# icetube_main.net
KiCad netlist of a schematic drawn in EAGLE
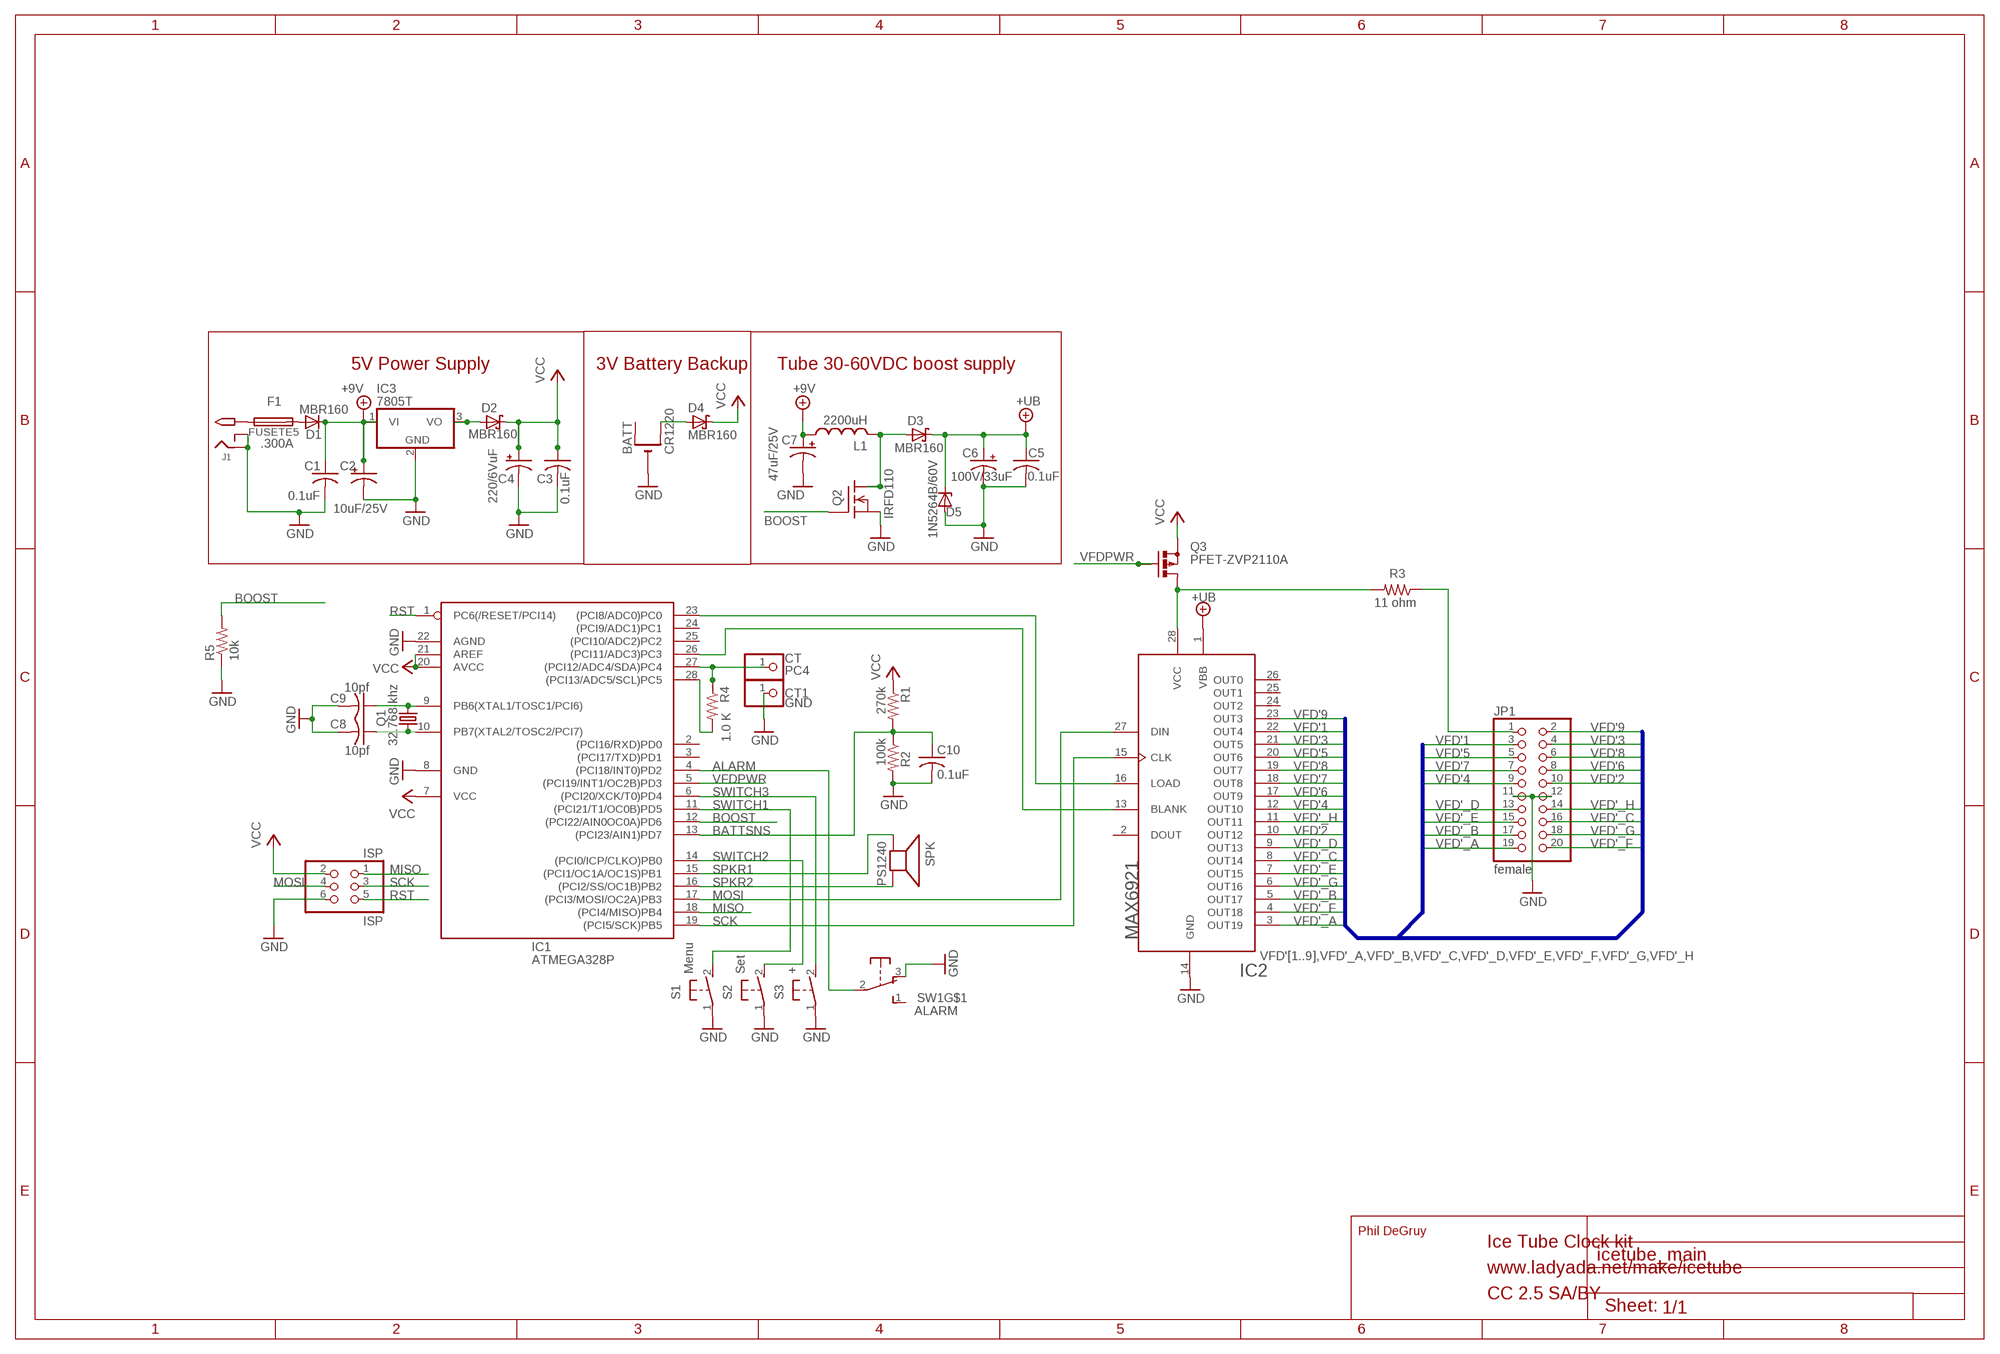
[diagram p0: schematic, sheet 1]

(export (version "E")
  (design (tool "Eeschema 10.0.6"))
  (components
    (comp (ref "BATT")
      (value "CR1220")
      (footprint "eagle-import:CR1220-THM")
      (libsource (lib "eagle-import") (part "CR1220THM"))
    )
    (comp (ref "C1")
      (value "0.1uF")
      (footprint "eagle-import:C025-025X050")
      (libsource (lib "eagle-import") (part "C-US025-025X050"))
    )
    (comp (ref "C2")
      (value "10uF/25V")
      (footprint "eagle-import:E2,5-6")
      (libsource (lib "eagle-import") (part "CPOL-USE2.5-6"))
    )
    (comp (ref "C3")
      (value "0.1uF")
      (footprint "eagle-import:C025-025X050")
      (libsource (lib "eagle-import") (part "C-US025-025X050"))
    )
    (comp (ref "C4")
      (value "220/6VuF")
      (footprint "eagle-import:E2,5-6")
      (libsource (lib "eagle-import") (part "CPOL-USE2.5-6"))
    )
    (comp (ref "C5")
      (value "0.1uF")
      (footprint "eagle-import:C025-024X044")
      (libsource (lib "eagle-import") (part "rcl-ez_C-US025-024X044"))
    )
    (comp (ref "C6")
      (value "100V/33uF")
      (footprint "eagle-import:E3,5-8")
      (libsource (lib "eagle-import") (part "rcl-ez_CPOL-USE3.5-8"))
    )
    (comp (ref "C7")
      (value "47uF/25V")
      (footprint "eagle-import:E2,5-6")
      (libsource (lib "eagle-import") (part "CPOL-USE2.5-6"))
    )
    (comp (ref "C8")
      (value "10pf")
      (footprint "eagle-import:C025-025X050")
      (libsource (lib "eagle-import") (part "C-US025-025X050"))
    )
    (comp (ref "C9")
      (value "10pf")
      (footprint "eagle-import:C025-025X050")
      (libsource (lib "eagle-import") (part "C-US025-025X050"))
    )
    (comp (ref "C10")
      (value "0.1uF")
      (footprint "eagle-import:C025-024X044")
      (libsource (lib "eagle-import") (part "rcl-ez_C-US025-024X044"))
    )
    (comp (ref "CT")
      (value "PC4")
      (footprint "eagle-import:1X01")
      (libsource (lib "eagle-import") (part "PINHD-1X1"))
    )
    (comp (ref "CT1")
      (value "GND")
      (footprint "eagle-import:1X01")
      (libsource (lib "eagle-import") (part "PINHD-1X1"))
    )
    (comp (ref "D1")
      (value "MBR160")
      (footprint "eagle-import:DO41-10")
      (libsource (lib "eagle-import") (part "1N4004"))
    )
    (comp (ref "D2")
      (value "MBR160")
      (footprint "eagle-import:DO41-10")
      (libsource (lib "eagle-import") (part "SCHOTTKY-DIODEDO41"))
    )
    (comp (ref "D3")
      (value "MBR160")
      (footprint "eagle-import:DO41-10")
      (libsource (lib "eagle-import") (part "SCHOTTKY-DIODEDO41"))
    )
    (comp (ref "D4")
      (value "MBR160")
      (footprint "eagle-import:DO41-10")
      (libsource (lib "eagle-import") (part "SCHOTTKY-DIODEDO41"))
    )
    (comp (ref "D5")
      (value "1N5264B/60V")
      (footprint "eagle-import:DO41Z10")
      (libsource (lib "eagle-import") (part "ZENER-DIODEDO41Z10"))
    )
    (comp (ref "F1")
      (value "FUSETE5")
      (footprint "eagle-import:TE5")
      (fields (field (name "MF") ".300A"))
      (libsource (lib "eagle-import") (part "FUSETE5"))
    )
    (comp (ref "IC1")
      (value "ATMEGA328P")
      (footprint "eagle-import:DIL28_3")
      (libsource (lib "eagle-import") (part "ATMEGA168PROUND"))
    )
    (comp (ref "IC2")
      (value "MAX6921")
      (footprint "eagle-import:PLCC-S28")
      (libsource (lib "eagle-import") (part "MAX6921"))
    )
    (comp (ref "IC3")
      (value "7805T")
      (footprint "eagle-import:TO220H")
      (libsource (lib "eagle-import") (part "78T05"))
    )
    (comp (ref "ISP")
      (value "ISP")
      (footprint "eagle-import:2X03")
      (libsource (lib "eagle-import") (part "PINHD-2X3"))
    )
    (comp (ref "J1")
      (value "2.1MMJACKTHM")
      (footprint "eagle-import:PJ-102A")
      (libsource (lib "eagle-import") (part "2.1MMJACKTHM"))
    )
    (comp (ref "JP1")
      (value "female")
      (footprint "eagle-import:2X10")
      (libsource (lib "eagle-import") (part "PINHD-2X10"))
    )
    (comp (ref "L1")
      (value "2200uH")
      (footprint "eagle-import:6000")
      (libsource (lib "eagle-import") (part "L"))
    )
    (comp (ref "Q1")
      (value "32.768 khz")
      (footprint "eagle-import:TC26V")
      (libsource (lib "eagle-import") (part "CRYTALTC26V"))
    )
    (comp (ref "Q2")
      (value "IRFD110")
      (footprint "eagle-import:DIL04")
      (libsource (lib "eagle-import") (part "IRFD110"))
    )
    (comp (ref "Q3")
      (value "PFET-ZVP2110A")
      (footprint "eagle-import:TO92-OVAL")
      (libsource (lib "eagle-import") (part "PFETZVP3306"))
    )
    (comp (ref "R1")
      (value "270k")
      (footprint "eagle-import:0207_10")
      (libsource (lib "eagle-import") (part "R-US_0207/10"))
    )
    (comp (ref "R2")
      (value "100k")
      (footprint "eagle-import:0207_10")
      (libsource (lib "eagle-import") (part "R-US_0207/10"))
    )
    (comp (ref "R3")
      (value "11 ohm")
      (footprint "eagle-import:0207_10")
      (libsource (lib "eagle-import") (part "R-US_0207/10"))
    )
    (comp (ref "R4")
      (value "1.0 K")
      (footprint "eagle-import:0207_5V")
      (libsource (lib "eagle-import") (part "R-US_0207/5V"))
    )
    (comp (ref "R5")
      (value "10k")
      (footprint "eagle-import:0207_5V")
      (libsource (lib "eagle-import") (part "R-US_0207/5V"))
    )
    (comp (ref "S1")
      (value "Menu")
      (footprint "eagle-import:B3F-31XX")
      (fields (field (name "MPN") "B3F-3100"))
      (libsource (lib "eagle-import") (part "31-XX"))
    )
    (comp (ref "S2")
      (value "Set")
      (footprint "eagle-import:B3F-31XX")
      (fields (field (name "MPN") "B3F-3100"))
      (libsource (lib "eagle-import") (part "31-XX"))
    )
    (comp (ref "S3")
      (value "+")
      (footprint "eagle-import:B3F-31XX")
      (fields (field (name "MPN") "B3F-3100"))
      (libsource (lib "eagle-import") (part "31-XX"))
    )
    (comp (ref "SPK")
      (value "PS1240")
      (footprint "eagle-import:PS12")
      (libsource (lib "eagle-import") (part "SPEAKER/PS12"))
    )
    (comp (ref "SW1")
      (value "ALARM")
      (footprint "eagle-import:OS102011MA1Q")
      (libsource (lib "eagle-import") (part "OS102011MA1Q"))
    )
  )
  (nets
    (net (code "1") (name "+9V") (class "Default")
      (node (ref "C1") (pin "1") (pinfunction "1_1") (pintype "passive"))
      (node (ref "C2") (pin "+") (pinfunction "+_+") (pintype "passive"))
      (node (ref "C7") (pin "+") (pinfunction "+_+") (pintype "passive"))
      (node (ref "D1") (pin "C") (pinfunction "C_C") (pintype "passive"))
      (node (ref "IC3") (pin "1") (pinfunction "VI_1") (pintype "input"))
      (node (ref "L1") (pin "1") (pinfunction "1_1") (pintype "passive"))
    )
    (net (code "2") (name "+UB") (class "Default")
      (node (ref "C5") (pin "1") (pinfunction "1_1") (pintype "passive"))
      (node (ref "C6") (pin "+") (pinfunction "+_+") (pintype "passive"))
      (node (ref "D3") (pin "C") (pinfunction "C_C") (pintype "passive"))
      (node (ref "D5") (pin "C") (pinfunction "C_C") (pintype "passive"))
      (node (ref "IC2") (pin "1") (pinfunction "VBB_1") (pintype "power_in"))
    )
    (net (code "3") (name "/ALARM") (class "Default")
      (node (ref "IC1") (pin "4") (pinfunction "(PCI18/INT0)PD2_4") (pintype "bidirectional"))
      (node (ref "SW1") (pin "2") (pinfunction "P_2") (pintype "passive"))
    )
    (net (code "4") (name "/BATTSNS") (class "Default")
      (node (ref "C10") (pin "1") (pinfunction "1_1") (pintype "passive"))
      (node (ref "IC1") (pin "13") (pinfunction "(PCI23/AIN1)PD7_13") (pintype "bidirectional"))
      (node (ref "R1") (pin "2") (pinfunction "2_2") (pintype "passive"))
      (node (ref "R2") (pin "1") (pinfunction "1_1") (pintype "passive"))
    )
    (net (code "5") (name "/BOOST") (class "Default")
      (node (ref "IC1") (pin "12") (pinfunction "(PCI22/AIN0OC0A)PD6_12") (pintype "bidirectional"))
      (node (ref "Q2") (pin "3") (pinfunction "G_3") (pintype "passive"))
      (node (ref "R5") (pin "2") (pinfunction "2_2") (pintype "passive"))
    )
    (net (code "6") (name "/MISO") (class "Default")
      (node (ref "IC1") (pin "18") (pinfunction "(PCI4/MISO)PB4_18") (pintype "bidirectional"))
      (node (ref "ISP") (pin "1") (pinfunction "1_1") (pintype "passive"))
    )
    (net (code "7") (name "/MOSI") (class "Default")
      (node (ref "IC1") (pin "17") (pinfunction "(PCI3/MOSI/OC2A)PB3_17") (pintype "bidirectional"))
      (node (ref "IC2") (pin "27") (pinfunction "DIN_27") (pintype "input"))
      (node (ref "ISP") (pin "4") (pinfunction "4_4") (pintype "passive"))
    )
    (net (code "8") (name "/RST") (class "Default")
      (node (ref "IC1") (pin "1") (pinfunction "PC6(/RESET/PCI14)_1") (pintype "bidirectional"))
      (node (ref "ISP") (pin "5") (pinfunction "5_5") (pintype "passive"))
    )
    (net (code "9") (name "/SCK") (class "Default")
      (node (ref "IC1") (pin "19") (pinfunction "(PCI5/SCK)PB5_19") (pintype "bidirectional"))
      (node (ref "IC2") (pin "15") (pinfunction "CLK_15") (pintype "input"))
      (node (ref "ISP") (pin "3") (pinfunction "3_3") (pintype "passive"))
    )
    (net (code "10") (name "/SPKR1") (class "Default")
      (node (ref "IC1") (pin "15") (pinfunction "(PCI1/OC1A/OC1S)PB1_15") (pintype "bidirectional"))
      (node (ref "SPK") (pin "P$1") (pinfunction "+_P$1") (pintype "passive"))
    )
    (net (code "11") (name "/SPKR2") (class "Default")
      (node (ref "IC1") (pin "16") (pinfunction "(PCI2/SS/OC1B)PB2_16") (pintype "bidirectional"))
      (node (ref "SPK") (pin "P$2") (pinfunction "-_P$2") (pintype "passive"))
    )
    (net (code "12") (name "/SWITCH1") (class "Default")
      (node (ref "IC1") (pin "11") (pinfunction "(PCI21/T1/OC0B)PD5_11") (pintype "bidirectional"))
      (node (ref "S1") (pin "2") (pinfunction "S_2") (pintype "passive"))
    )
    (net (code "13") (name "/SWITCH2") (class "Default")
      (node (ref "IC1") (pin "14") (pinfunction "(PCI0/ICP/CLKO)PB0_14") (pintype "bidirectional"))
      (node (ref "S2") (pin "2") (pinfunction "S_2") (pintype "passive"))
    )
    (net (code "14") (name "/SWITCH3") (class "Default")
      (node (ref "IC1") (pin "6") (pinfunction "(PCI20/XCK/T0)PD4_6") (pintype "bidirectional"))
      (node (ref "S3") (pin "2") (pinfunction "S_2") (pintype "passive"))
    )
    (net (code "15") (name "/VFD'1") (class "Default")
      (node (ref "IC2") (pin "22") (pinfunction "OUT4_22") (pintype "output"))
      (node (ref "JP1") (pin "3") (pinfunction "3_3") (pintype "passive"))
    )
    (net (code "16") (name "/VFD'2") (class "Default")
      (node (ref "IC2") (pin "10") (pinfunction "OUT12_10") (pintype "output"))
      (node (ref "JP1") (pin "10") (pinfunction "10_10") (pintype "passive"))
    )
    (net (code "17") (name "/VFD'3") (class "Default")
      (node (ref "IC2") (pin "21") (pinfunction "OUT5_21") (pintype "output"))
      (node (ref "JP1") (pin "4") (pinfunction "4_4") (pintype "passive"))
    )
    (net (code "18") (name "/VFD'4") (class "Default")
      (node (ref "IC2") (pin "12") (pinfunction "OUT10_12") (pintype "output"))
      (node (ref "JP1") (pin "9") (pinfunction "9_9") (pintype "passive"))
    )
    (net (code "19") (name "/VFD'5") (class "Default")
      (node (ref "IC2") (pin "20") (pinfunction "OUT6_20") (pintype "output"))
      (node (ref "JP1") (pin "5") (pinfunction "5_5") (pintype "passive"))
    )
    (net (code "20") (name "/VFD'6") (class "Default")
      (node (ref "IC2") (pin "17") (pinfunction "OUT9_17") (pintype "output"))
      (node (ref "JP1") (pin "8") (pinfunction "8_8") (pintype "passive"))
    )
    (net (code "21") (name "/VFD'7") (class "Default")
      (node (ref "IC2") (pin "18") (pinfunction "OUT8_18") (pintype "output"))
      (node (ref "JP1") (pin "7") (pinfunction "7_7") (pintype "passive"))
    )
    (net (code "22") (name "/VFD'8") (class "Default")
      (node (ref "IC2") (pin "19") (pinfunction "OUT7_19") (pintype "output"))
      (node (ref "JP1") (pin "6") (pinfunction "6_6") (pintype "passive"))
    )
    (net (code "23") (name "/VFD'9") (class "Default")
      (node (ref "IC2") (pin "23") (pinfunction "OUT3_23") (pintype "output"))
      (node (ref "JP1") (pin "2") (pinfunction "2_2") (pintype "passive"))
    )
    (net (code "24") (name "/VFD'_A") (class "Default")
      (node (ref "IC2") (pin "3") (pinfunction "OUT19_3") (pintype "output"))
      (node (ref "JP1") (pin "19") (pinfunction "19_19") (pintype "passive"))
    )
    (net (code "25") (name "/VFD'_B") (class "Default")
      (node (ref "IC2") (pin "5") (pinfunction "OUT17_5") (pintype "output"))
      (node (ref "JP1") (pin "17") (pinfunction "17_17") (pintype "passive"))
    )
    (net (code "26") (name "/VFD'_C") (class "Default")
      (node (ref "IC2") (pin "8") (pinfunction "OUT14_8") (pintype "output"))
      (node (ref "JP1") (pin "16") (pinfunction "16_16") (pintype "passive"))
    )
    (net (code "27") (name "/VFD'_D") (class "Default")
      (node (ref "IC2") (pin "9") (pinfunction "OUT13_9") (pintype "output"))
      (node (ref "JP1") (pin "13") (pinfunction "13_13") (pintype "passive"))
    )
    (net (code "28") (name "/VFD'_E") (class "Default")
      (node (ref "IC2") (pin "7") (pinfunction "OUT15_7") (pintype "output"))
      (node (ref "JP1") (pin "15") (pinfunction "15_15") (pintype "passive"))
    )
    (net (code "29") (name "/VFD'_F") (class "Default")
      (node (ref "IC2") (pin "4") (pinfunction "OUT18_4") (pintype "output"))
      (node (ref "JP1") (pin "20") (pinfunction "20_20") (pintype "passive"))
    )
    (net (code "30") (name "/VFD'_G") (class "Default")
      (node (ref "IC2") (pin "6") (pinfunction "OUT16_6") (pintype "output"))
      (node (ref "JP1") (pin "18") (pinfunction "18_18") (pintype "passive"))
    )
    (net (code "31") (name "/VFD'_H") (class "Default")
      (node (ref "IC2") (pin "11") (pinfunction "OUT11_11") (pintype "output"))
      (node (ref "JP1") (pin "14") (pinfunction "14_14") (pintype "passive"))
    )
    (net (code "32") (name "/VFDPWR") (class "Default")
      (node (ref "IC1") (pin "5") (pinfunction "(PCI19/INT1/OC2B)PD3_5") (pintype "bidirectional"))
      (node (ref "Q3") (pin "2") (pinfunction "G_2") (pintype "passive"))
    )
    (net (code "34") (name "GND") (class "Default")
      (node (ref "BATT") (pin "-") (pinfunction "-_-") (pintype "passive"))
      (node (ref "C1") (pin "2") (pinfunction "2_2") (pintype "passive"))
      (node (ref "C10") (pin "2") (pinfunction "2_2") (pintype "passive"))
      (node (ref "C2") (pin "-") (pinfunction "-_-") (pintype "passive"))
      (node (ref "C3") (pin "2") (pinfunction "2_2") (pintype "passive"))
      (node (ref "C4") (pin "-") (pinfunction "-_-") (pintype "passive"))
      (node (ref "C5") (pin "2") (pinfunction "2_2") (pintype "passive"))
      (node (ref "C6") (pin "-") (pinfunction "-_-") (pintype "passive"))
      (node (ref "C7") (pin "-") (pinfunction "-_-") (pintype "passive"))
      (node (ref "C8") (pin "2") (pinfunction "2_2") (pintype "passive"))
      (node (ref "C9") (pin "2") (pinfunction "2_2") (pintype "passive"))
      (node (ref "CT1") (pin "1") (pinfunction "1_1") (pintype "passive"))
      (node (ref "D5") (pin "A") (pinfunction "A_A") (pintype "passive"))
      (node (ref "IC1") (pin "22") (pinfunction "AGND_22") (pintype "bidirectional"))
      (node (ref "IC1") (pin "8") (pinfunction "GND_8") (pintype "bidirectional"))
      (node (ref "IC2") (pin "14") (pinfunction "GND_14") (pintype "power_in"))
      (node (ref "IC3") (pin "2") (pinfunction "GND_2") (pintype "passive"))
      (node (ref "ISP") (pin "6") (pinfunction "6_6") (pintype "passive"))
      (node (ref "J1") (pin "RING") (pinfunction "RING_RING") (pintype "bidirectional"))
      (node (ref "J1") (pin "RING_SW") (pinfunction "RING_SW_RING_SW") (pintype "bidirectional"))
      (node (ref "JP1") (pin "11") (pinfunction "11_11") (pintype "passive"))
      (node (ref "JP1") (pin "12") (pinfunction "12_12") (pintype "passive"))
      (node (ref "Q2") (pin "4") (pinfunction "S_4") (pintype "passive"))
      (node (ref "R2") (pin "2") (pinfunction "2_2") (pintype "passive"))
      (node (ref "R5") (pin "1") (pinfunction "1_1") (pintype "passive"))
      (node (ref "S1") (pin "1") (pinfunction "P_1") (pintype "passive"))
      (node (ref "S2") (pin "1") (pinfunction "P_1") (pintype "passive"))
      (node (ref "S3") (pin "1") (pinfunction "P_1") (pintype "passive"))
      (node (ref "SW1") (pin "3") (pinfunction "O_3") (pintype "passive"))
    )
    (net (code "35") (name "Net-(BATT-+1)") (class "Default")
      (node (ref "BATT") (pin "+2") (pinfunction "+1_+2") (pintype "passive"))
      (node (ref "D4") (pin "A") (pinfunction "A_A") (pintype "passive"))
    )
    (net (code "36") (name "Net-(D1-PadA)") (class "Default")
      (node (ref "D1") (pin "A") (pinfunction "A_A") (pintype "passive"))
      (node (ref "F1") (pin "2") (pinfunction "2_2") (pintype "passive"))
    )
    (net (code "37") (name "Net-(F1-Pad1)") (class "Default")
      (node (ref "F1") (pin "1") (pinfunction "1_1") (pintype "passive"))
      (node (ref "J1") (pin "TIP") (pinfunction "TIP_TIP") (pintype "bidirectional"))
    )
    (net (code "38") (name "Net-(IC1-(PCI8{slash}ADC0)PC0)") (class "Default")
      (node (ref "IC1") (pin "23") (pinfunction "(PCI8/ADC0)PC0_23") (pintype "bidirectional"))
      (node (ref "IC2") (pin "16") (pinfunction "LOAD_16") (pintype "input"))
    )
    (net (code "39") (name "Net-(IC1-(PCI11{slash}ADC3)PC3)") (class "Default")
      (node (ref "IC1") (pin "26") (pinfunction "(PCI11/ADC3)PC3_26") (pintype "bidirectional"))
      (node (ref "IC2") (pin "13") (pinfunction "BLANK_13") (pintype "input"))
    )
    (net (code "40") (name "Net-(IC1-(PCI12{slash}ADC4{slash}SDA)PC4)") (class "Default")
      (node (ref "CT") (pin "1") (pinfunction "1_1") (pintype "passive"))
      (node (ref "IC1") (pin "27") (pinfunction "(PCI12/ADC4/SDA)PC4_27") (pintype "bidirectional"))
      (node (ref "R4") (pin "1") (pinfunction "1_1") (pintype "passive"))
    )
    (net (code "41") (name "Net-(IC1-(PCI13{slash}ADC5{slash}SCL)PC5)") (class "Default")
      (node (ref "IC1") (pin "28") (pinfunction "(PCI13/ADC5/SCL)PC5_28") (pintype "bidirectional"))
      (node (ref "R4") (pin "2") (pinfunction "2_2") (pintype "passive"))
    )
    (net (code "42") (name "Net-(IC1-PB6(XTAL1{slash}TOSC1{slash}PCI6))") (class "Default")
      (node (ref "C9") (pin "1") (pinfunction "1_1") (pintype "passive"))
      (node (ref "IC1") (pin "9") (pinfunction "PB6(XTAL1/TOSC1/PCI6)_9") (pintype "bidirectional"))
      (node (ref "Q1") (pin "2") (pinfunction "2_2") (pintype "passive"))
    )
    (net (code "43") (name "Net-(IC1-PB7(XTAL2{slash}TOSC2{slash}PCI7))") (class "Default")
      (node (ref "C8") (pin "1") (pinfunction "1_1") (pintype "passive"))
      (node (ref "IC1") (pin "10") (pinfunction "PB7(XTAL2/TOSC2/PCI7)_10") (pintype "bidirectional"))
      (node (ref "Q1") (pin "1") (pinfunction "1_1") (pintype "passive"))
    )
    (net (code "44") (name "Net-(IC2-VCC)") (class "Default")
      (node (ref "IC2") (pin "28") (pinfunction "VCC_28") (pintype "power_in"))
      (node (ref "Q3") (pin "3") (pinfunction "D_3") (pintype "passive"))
      (node (ref "R3") (pin "2") (pinfunction "2_2") (pintype "passive"))
    )
    (net (code "45") (name "Net-(IC3-VO)") (class "Default")
      (node (ref "D2") (pin "A") (pinfunction "A_A") (pintype "passive"))
      (node (ref "IC3") (pin "3") (pinfunction "VO_3") (pintype "passive"))
    )
    (net (code "46") (name "Net-(JP1-Pad1)") (class "Default")
      (node (ref "JP1") (pin "1") (pinfunction "1_1") (pintype "passive"))
      (node (ref "R3") (pin "1") (pinfunction "1_1") (pintype "passive"))
    )
    (net (code "47") (name "Net-(Q2-D)") (class "Default")
      (node (ref "D3") (pin "A") (pinfunction "A_A") (pintype "passive"))
      (node (ref "L1") (pin "2") (pinfunction "2_2") (pintype "passive"))
      (node (ref "Q2") (pin "1") (pinfunction "D_1") (pintype "passive"))
      (node (ref "Q2") (pin "2") (pinfunction "D1_2") (pintype "passive"))
    )
    (net (code "48") (name "VCC") (class "Default")
      (node (ref "C3") (pin "1") (pinfunction "1_1") (pintype "passive"))
      (node (ref "C4") (pin "+") (pinfunction "+_+") (pintype "passive"))
      (node (ref "D2") (pin "C") (pinfunction "C_C") (pintype "passive"))
      (node (ref "D4") (pin "C") (pinfunction "C_C") (pintype "passive"))
      (node (ref "IC1") (pin "20") (pinfunction "AVCC_20") (pintype "bidirectional"))
      (node (ref "IC1") (pin "21") (pinfunction "AREF_21") (pintype "bidirectional"))
      (node (ref "IC1") (pin "7") (pinfunction "VCC_7") (pintype "bidirectional"))
      (node (ref "ISP") (pin "2") (pinfunction "2_2") (pintype "passive"))
      (node (ref "Q3") (pin "1") (pinfunction "S_1") (pintype "passive"))
      (node (ref "R1") (pin "1") (pinfunction "1_1") (pintype "passive"))
    )
    (net (code "49") (name "unconnected-(BATT-+-Pad+1)") (class "Default")
      (node (ref "BATT") (pin "+1") (pinfunction "+_+1") (pintype "passive"))
    )
    (net (code "50") (name "unconnected-(IC1-(PCI9{slash}ADC1)PC1-Pad24)") (class "Default")
      (node (ref "IC1") (pin "24") (pinfunction "(PCI9/ADC1)PC1_24") (pintype "bidirectional"))
    )
    (net (code "51") (name "unconnected-(IC1-(PCI10{slash}ADC2)PC2-Pad25)") (class "Default")
      (node (ref "IC1") (pin "25") (pinfunction "(PCI10/ADC2)PC2_25") (pintype "bidirectional"))
    )
    (net (code "52") (name "unconnected-(IC1-(PCI16{slash}RXD)PD0-Pad2)") (class "Default")
      (node (ref "IC1") (pin "2") (pinfunction "(PCI16/RXD)PD0_2") (pintype "bidirectional"))
    )
    (net (code "53") (name "unconnected-(IC1-(PCI17{slash}TXD)PD1-Pad3)") (class "Default")
      (node (ref "IC1") (pin "3") (pinfunction "(PCI17/TXD)PD1_3") (pintype "bidirectional"))
    )
    (net (code "54") (name "unconnected-(IC2-DOUT-Pad2)") (class "Default")
      (node (ref "IC2") (pin "2") (pinfunction "DOUT_2") (pintype "output"))
    )
    (net (code "55") (name "unconnected-(IC2-OUT0-Pad26)") (class "Default")
      (node (ref "IC2") (pin "26") (pinfunction "OUT0_26") (pintype "output"))
    )
    (net (code "56") (name "unconnected-(IC2-OUT1-Pad25)") (class "Default")
      (node (ref "IC2") (pin "25") (pinfunction "OUT1_25") (pintype "output"))
    )
    (net (code "57") (name "unconnected-(IC2-OUT2-Pad24)") (class "Default")
      (node (ref "IC2") (pin "24") (pinfunction "OUT2_24") (pintype "output"))
    )
    (net (code "58") (name "unconnected-(SW1A-S-Pad1)") (class "Default")
      (node (ref "SW1") (pin "1") (pinfunction "S_1") (pintype "passive"))
    )
  )
)
